# SCH_Solder_2025-04-27_2.net
KiCad netlist of a schematic drawn in EasyEDA
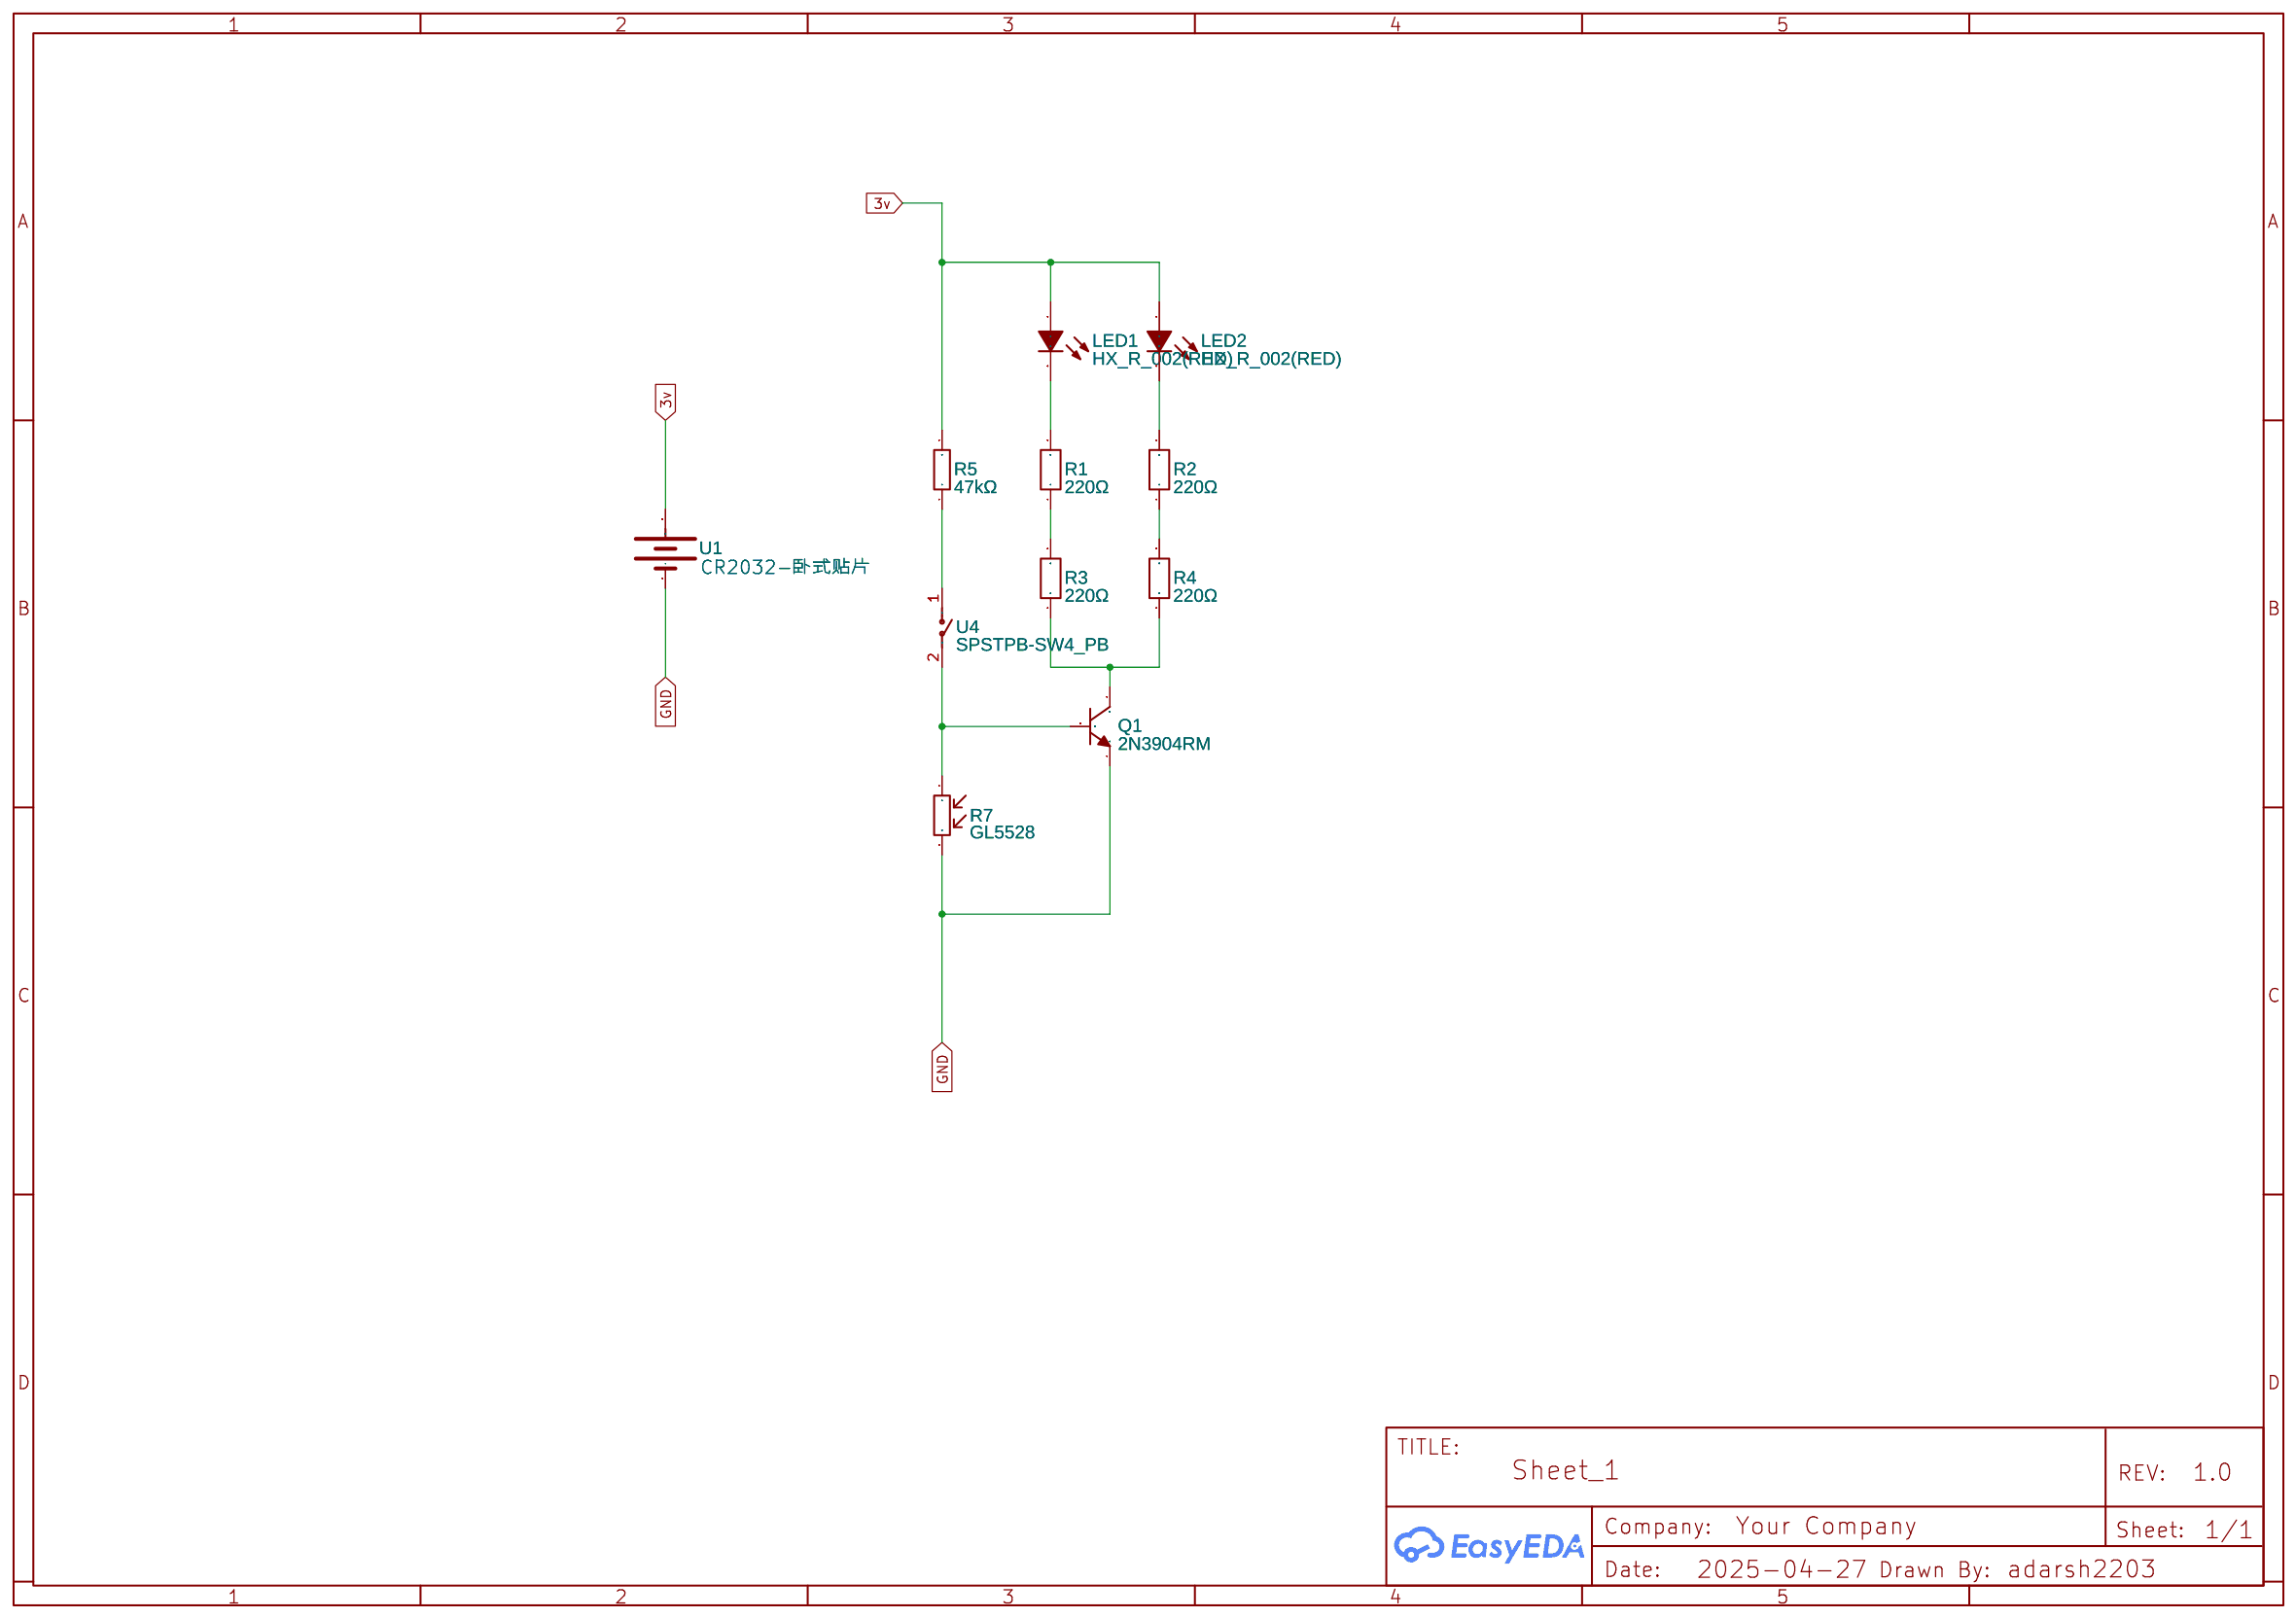
[diagram p0: schematic sheet]

(export (version "E")
  (design (tool "Eeschema 10.0.6"))
  (components
    (comp (ref "LED1") (value "HX_R_002(RED)") (libsource (lib "") (part "HX_R_002(RED)")))
    (comp (ref "LED2") (value "HX_R_002(RED)") (libsource (lib "") (part "HX_R_002(RED)")))
    (comp (ref "Q1")
      (value "2N3904RM")
      (fields (field (name "Manufacturer") "onsemi(安森美)"))
      (libsource (lib "") (part "2N3904RM"))
    )
    (comp (ref "R1")
      (value "220Ω")
      (fields
        (field (name "Manufacturer Part") "CR0805J220RP05Z")
        (field (name "Manufacturer") "EVER OHMS(天二科技)")
      )
      (libsource (lib "") (part "CR0805J220RP05Z"))
    )
    (comp (ref "R2")
      (value "220Ω")
      (fields
        (field (name "Manufacturer Part") "CR0805J220RP05Z")
        (field (name "Manufacturer") "EVER OHMS(天二科技)")
      )
      (libsource (lib "") (part "CR0805J220RP05Z"))
    )
    (comp (ref "R3")
      (value "220Ω")
      (fields
        (field (name "Manufacturer Part") "CR0805J220RP05Z")
        (field (name "Manufacturer") "EVER OHMS(天二科技)")
      )
      (libsource (lib "") (part "CR0805J220RP05Z"))
    )
    (comp (ref "R4")
      (value "220Ω")
      (fields
        (field (name "Manufacturer Part") "CR0805J220RP05Z")
        (field (name "Manufacturer") "EVER OHMS(天二科技)")
      )
      (libsource (lib "") (part "CR0805J220RP05Z"))
    )
    (comp (ref "R5")
      (value "47kΩ")
      (fields
        (field (name "Manufacturer Part") "0603WAJ0473T5E")
        (field (name "Manufacturer") "UNI-ROYAL(厚声)")
      )
      (libsource (lib "") (part "0603WAJ0473T5E"))
    )
    (comp (ref "R7")
      (value "GL5528")
      (fields (field (name "Manufacturer") "森霸"))
      (libsource (lib "") (part "GL5528"))
    )
    (comp (ref "U1") (value "CR2032-卧式贴片") (libsource (lib "") (part "CR2032-卧式贴片")))
    (comp (ref "U4") (value "SPSTPB-SW4_PB") (libsource (lib "") (part "SPSTPB-SW4_PB")))
  )
  (nets
    (net (code "1") (name "3v") (class "Default")
      (node (ref "LED1") (pin "1") (pinfunction "A_1") (pintype "input"))
      (node (ref "LED2") (pin "1") (pinfunction "A_1") (pintype "input"))
      (node (ref "R5") (pin "2") (pinfunction "2_2") (pintype "input"))
      (node (ref "U1") (pin "2") (pinfunction "+_2") (pintype "passive"))
    )
    (net (code "2") (name "GND") (class "Default")
      (node (ref "Q1") (pin "1") (pinfunction "E_1") (pintype "input"))
      (node (ref "R7") (pin "2") (pinfunction "2_2") (pintype "input"))
      (node (ref "U1") (pin "1") (pinfunction "-_1") (pintype "passive"))
    )
    (net (code "3") (name "Net-(LED1-C)") (class "Default")
      (node (ref "LED1") (pin "2") (pinfunction "C_2") (pintype "input"))
      (node (ref "R1") (pin "2") (pinfunction "2_2") (pintype "unspecified"))
    )
    (net (code "4") (name "Net-(LED2-C)") (class "Default")
      (node (ref "LED2") (pin "2") (pinfunction "C_2") (pintype "input"))
      (node (ref "R2") (pin "2") (pinfunction "2_2") (pintype "unspecified"))
    )
    (net (code "5") (name "Net-(Q1-B)") (class "Default")
      (node (ref "Q1") (pin "2") (pinfunction "B_2") (pintype "input"))
      (node (ref "R7") (pin "1") (pinfunction "1_1") (pintype "input"))
      (node (ref "U4") (pin "2") (pinfunction "2_2") (pintype "unspecified"))
    )
    (net (code "6") (name "Net-(Q1-C)") (class "Default")
      (node (ref "Q1") (pin "3") (pinfunction "C_3") (pintype "input"))
      (node (ref "R3") (pin "1") (pinfunction "1_1") (pintype "unspecified"))
      (node (ref "R4") (pin "1") (pinfunction "1_1") (pintype "unspecified"))
    )
    (net (code "7") (name "Net-(R1-Pad1)") (class "Default")
      (node (ref "R1") (pin "1") (pinfunction "1_1") (pintype "unspecified"))
      (node (ref "R3") (pin "2") (pinfunction "2_2") (pintype "unspecified"))
    )
    (net (code "8") (name "Net-(R2-Pad1)") (class "Default")
      (node (ref "R2") (pin "1") (pinfunction "1_1") (pintype "unspecified"))
      (node (ref "R4") (pin "2") (pinfunction "2_2") (pintype "unspecified"))
    )
    (net (code "9") (name "Net-(R5-Pad1)") (class "Default")
      (node (ref "R5") (pin "1") (pinfunction "1_1") (pintype "input"))
      (node (ref "U4") (pin "1") (pinfunction "1_1") (pintype "unspecified"))
    )
  )
)
